# ADC_Filter.net
KiCad netlist of a schematic drawn in Altium Designer
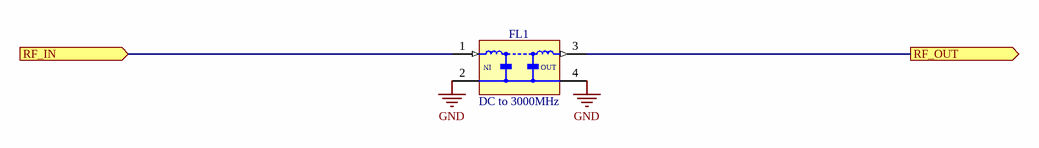
[diagram p0: ADC_Filter.SchDoc]

(export (version "E")
  (design (tool "Eeschema 10.0.6"))
  (components
    (comp (ref "FL1")
      (value "DC to 3000MHz")
      (footprint "FIL_MINI-CIRCUITS_FV1206")
      (description "50 Ohm DC to 3000MHz Low Pass Filter")
      (fields
        (field (name "PART NUMBER") "FIL_MINI-CIRCUITS_LFCN-3000+")
        (field (name "MANUFACTURER") "MINI-CIRCUITS")
        (field (name "AUTHOR") "CERN DEM JLC")
      )
      (libsource (lib "Inductors & Transformers") (part "FIL_MINI-CIRCUITS_LFCN-3000+"))
    )
  )
  (nets
    (net (code "1") (name "/RF_IN") (class "Default")
      (node (ref "FL1") (pin "1") (pinfunction "RFIN_1") (pintype "input"))
    )
    (net (code "2") (name "/RF_OUT") (class "Default")
      (node (ref "FL1") (pin "3") (pinfunction "RFOUT_3") (pintype "output"))
    )
    (net (code "3") (name "GND") (class "Default")
      (node (ref "FL1") (pin "2") (pinfunction "GND_2") (pintype "power_in"))
      (node (ref "FL1") (pin "4") (pinfunction "GND_4") (pintype "power_in"))
    )
  )
)
